# DM1090FFC_Power_Supply.net
KiCad netlist of a schematic drawn in Altium Designer
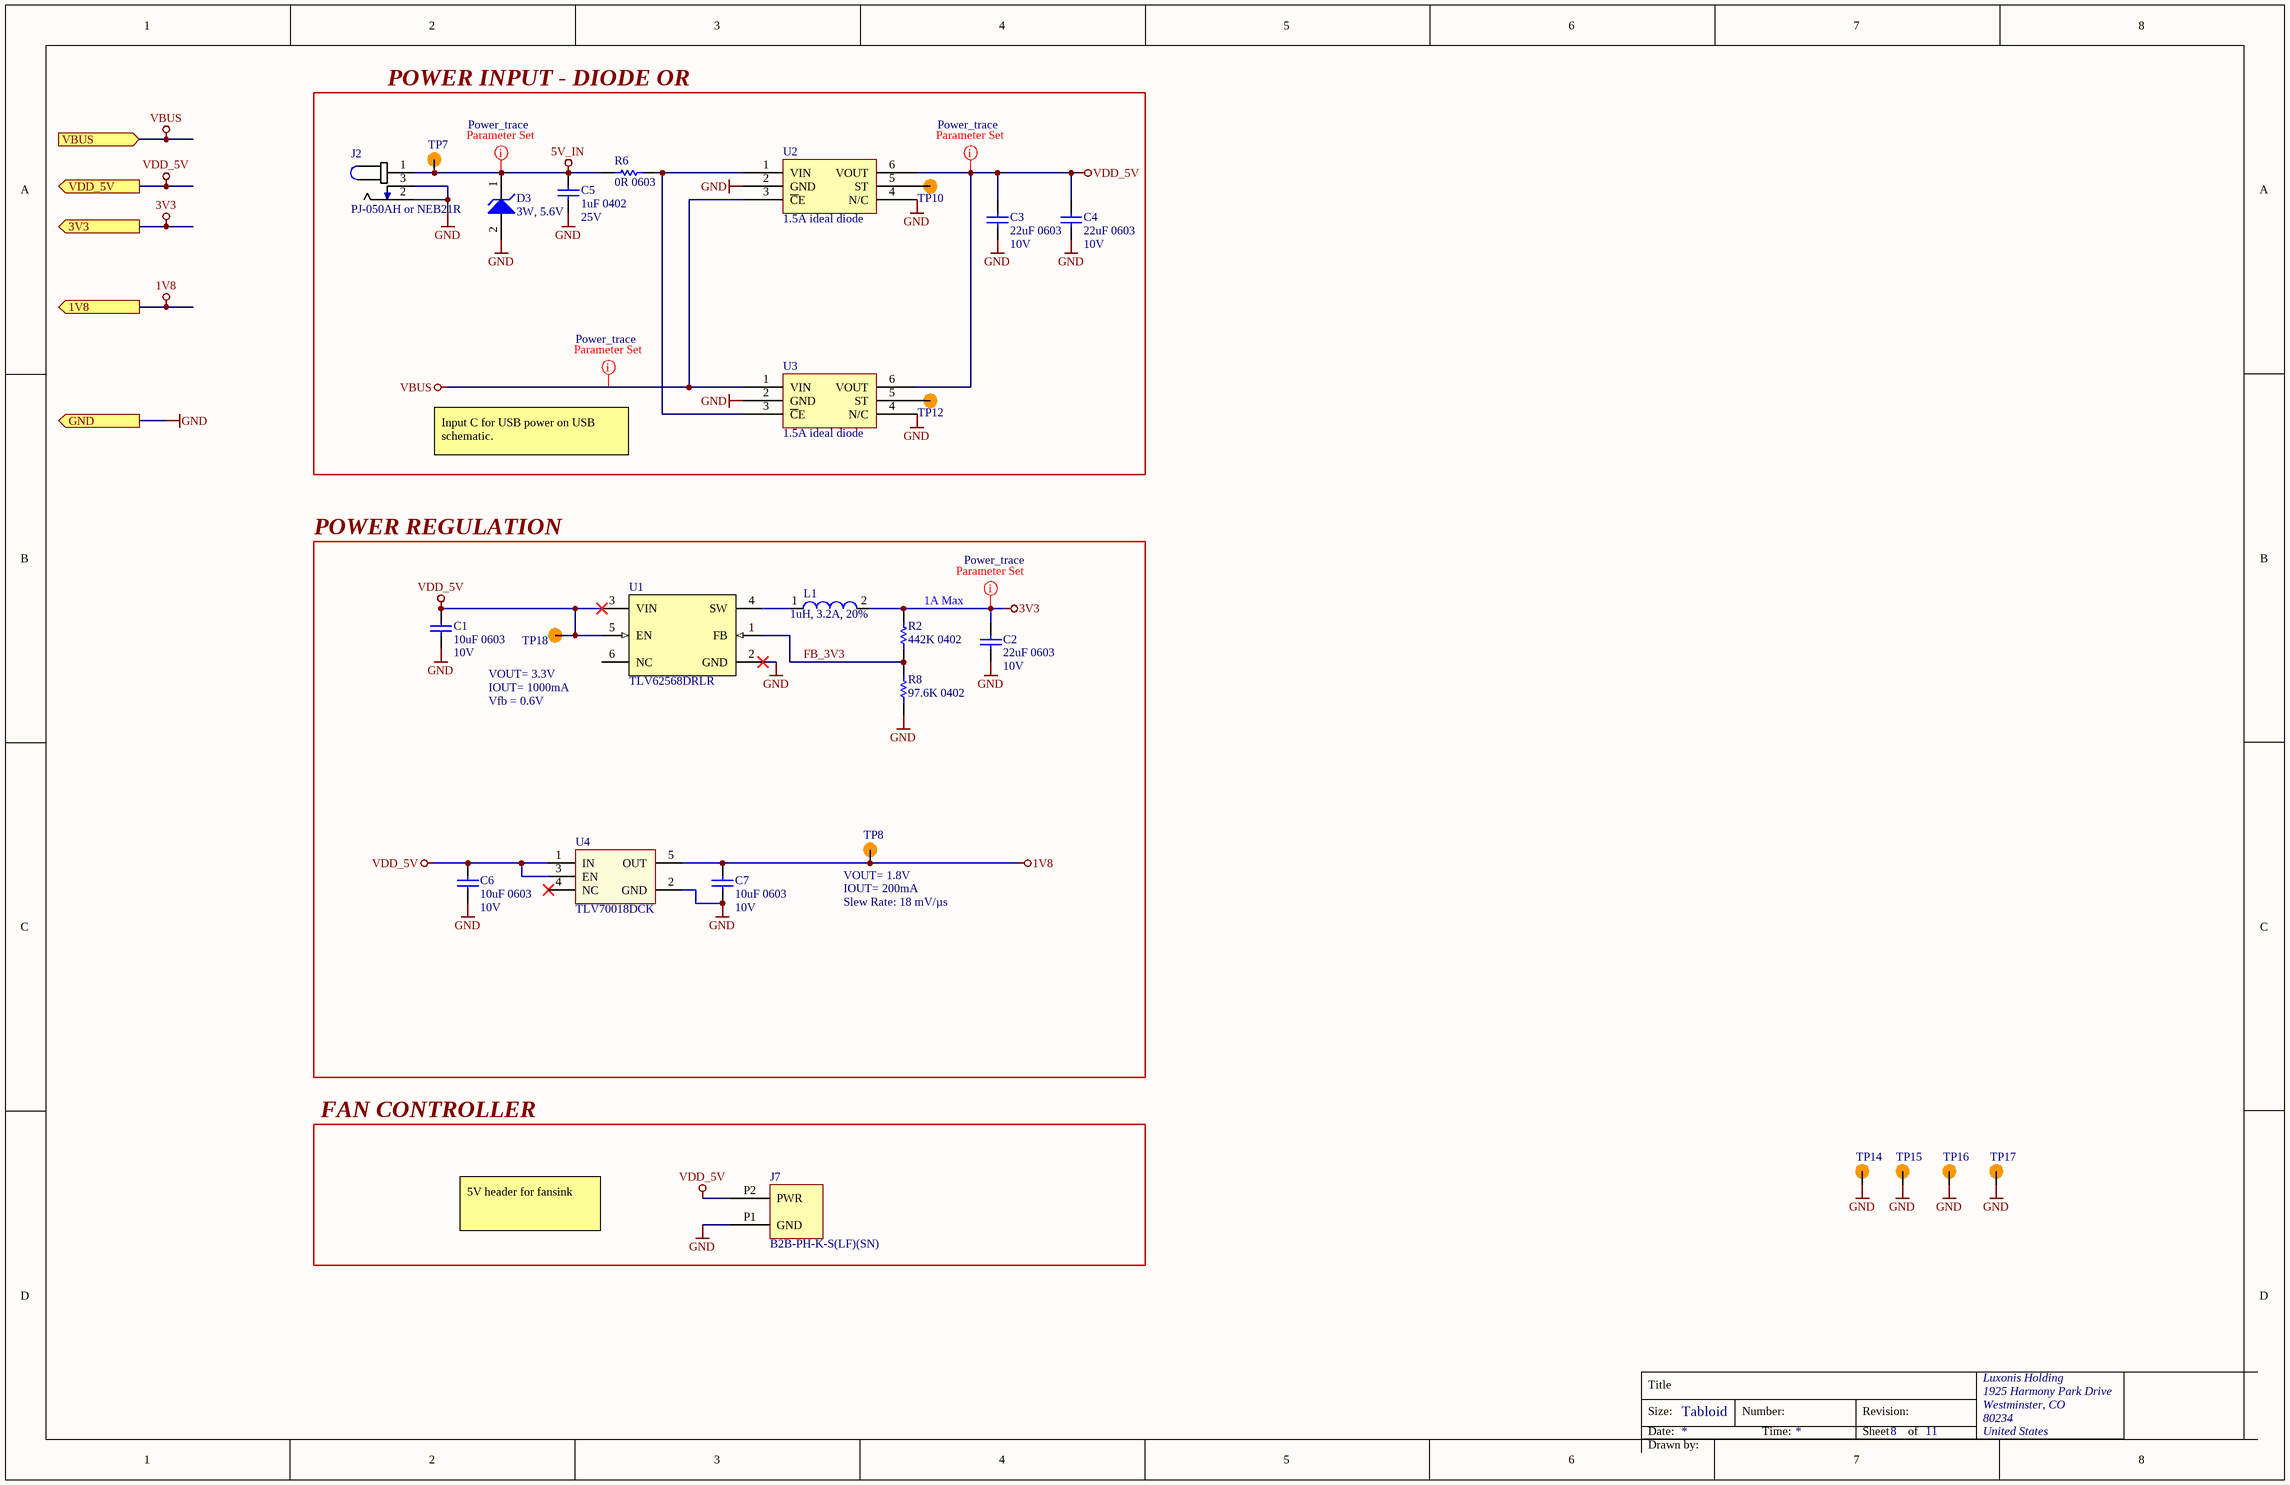
[diagram p0: DM1090FFC_Power_Supply.SchDoc]

(export (version "E")
  (design (tool "Eeschema 10.0.6"))
  (components
    (comp (ref "C1")
      (value "10uF 0603")
      (footprint "CAP_Altium_Vault_Generic:CAPC0603(1608)100_L")
      (description "CAP CER 10UF 10V X5R 0603 20%")
      (fields (field (name "TOLERANCE") "20%") (field (name "VOLTAGE RATING") "10V"))
      (libsource (lib "LuxonisMaster") (part "GRM188R61A106ME69D"))
    )
    (comp (ref "C2")
      (value "22uF 0603")
      (footprint "CAP_Altium_Vault_Generic:CAPC0603(1608)100_N")
      (description "CAP CER 22UF 10V X5R 0603 20%")
      (fields (field (name "TOLERANCE") "20%") (field (name "VOLTAGE RATING") "10V"))
      (libsource (lib "LuxonisMaster") (part "GRM188R61A226ME15D"))
    )
    (comp (ref "C3")
      (value "22uF 0603")
      (footprint "CAP_Altium_Vault_Generic:CAPC0603(1608)100_N")
      (description "CAP CER 22UF 10V X5R 0603 20%")
      (fields (field (name "TOLERANCE") "20%") (field (name "VOLTAGE RATING") "10V"))
      (libsource (lib "LuxonisMaster") (part "GRM188R61A226ME15D"))
    )
    (comp (ref "C4")
      (value "22uF 0603")
      (footprint "CAP_Altium_Vault_Generic:CAPC0603(1608)100_N")
      (description "CAP CER 22UF 10V X5R 0603 20%")
      (fields (field (name "TOLERANCE") "20%") (field (name "VOLTAGE RATING") "10V"))
      (libsource (lib "LuxonisMaster") (part "GRM188R61A226ME15D"))
    )
    (comp (ref "C5")
      (value "1uF 0402")
      (footprint "CAP_Altium_Vault_Generic:CAPC0402(1005)70_N")
      (description "CAP CER 1UF 25V X5R 0402 10%")
      (fields
        (field (name "TOLERANCE") "10%")
        (field (name "VOLTAGE") "25V")
        (field (name "VOLTAGE RATING") "25V")
      )
      (libsource (lib "LuxonisMaster") (part "GRM155R61E105KA12D"))
    )
    (comp (ref "C6")
      (value "10uF 0603")
      (footprint "CAP_Altium_Vault_Generic:CAPC0603(1608)100_L")
      (description "CAP CER 10UF 10V X5R 0603 20%")
      (fields (field (name "TOLERANCE") "20%") (field (name "VOLTAGE RATING") "10V"))
      (libsource (lib "LuxonisMaster") (part "GRM188R61A106ME69D"))
    )
    (comp (ref "C7")
      (value "10uF 0603")
      (footprint "CAP_Altium_Vault_Generic:CAPC0603(1608)100_L")
      (description "CAP CER 10UF 10V X5R 0603 20%")
      (fields (field (name "TOLERANCE") "20%") (field (name "VOLTAGE RATING") "10V"))
      (libsource (lib "LuxonisMaster") (part "GRM188R61A106ME69D"))
    )
    (comp (ref "D3")
      (value "3W, 5.6V")
      (footprint "DM1092_R0M0E0:1SMB5919BT3G")
      (description "DIODE ZENER 5.6V 3W SMB")
      (fields (field (name "TOLERANCE") "5%"))
      (libsource (lib "DM1092_R0M0E0") (part "1SMB5919BT3G"))
    )
    (comp (ref "J2")
      (value "PJ-050AH or NEB21R")
      (footprint "LuxonisMaster:PJ-050AH/NEB21R_COMBO")
      (description "CONN POWER PIN 2 POS RA PTH Barrel jack 2.1mm x 5.5mm combo footprint")
      (libsource (lib "LuxonisMaster") (part "PJ-050AH/NEB21R_COMBO"))
    )
    (comp (ref "J7")
      (value "B2B-PH-K-S(LF)(SN)")
      (footprint "LuxonisMaster:B2B-PH-K-S(LF)(SN)")
      (description "CONN HEADER VERT 2POS 2MM")
      (libsource (lib "LuxonisMaster") (part "B2B-PH-K-S(LF)(SN)"))
    )
    (comp (ref "L1")
      (value "1uH, 3.2A, 20%")
      (footprint "LuxonisMaster:DFE252012P-1R0M=P2")
      (description "FIXED IND 1UH 3.2A 42 MOHM SMD")
      (fields
        (field (name "MANUFACTURER") "Murata")
        (field (name "MANUFACTURER PART NUMBER") "DFE252012P-1R0M=P2")
      )
      (libsource (lib "LuxonisMaster") (part "DFE252012P-1R0M=P2"))
    )
    (comp (ref "R2")
      (value "442K 0402")
      (footprint "RES_Altium_Vault_Generic:RESC0402(1005)_N")
      (description "RES SMD 442K OHM 1% 1/16W 0402")
      (fields (field (name "TOLERANCE") "1%"))
      (libsource (lib "BW1092_R0M0E0") (part "CRCW0402442KFKED"))
    )
    (comp (ref "R6")
      (value "0R 0603")
      (footprint "RES_Altium_Vault_Generic:RESC0603(1608)_N")
      (fields (field (name "TOLERANCE") "5%"))
      (libsource (lib "LuxonisMaster") (part "CRCW06030000Z0EA"))
    )
    (comp (ref "R8")
      (value "97.6K 0402")
      (footprint "RES_Altium_Vault_Generic:RESC0402(1005)_N")
      (description "RES SMD 97.6K OHM 1% 1/16W 0402")
      (fields (field (name "TOLERANCE") "1%"))
      (libsource (lib "BW1092_R0M0E0") (part "CRCW040297K6FKED"))
    )
    (comp (ref "TP7")
      (value "TP100_200_NS")
      (footprint "LuxonisMaster:TP100_200_NS")
      (libsource (lib "LuxonisMaster") (part "TEST_POINT"))
    )
    (comp (ref "TP8")
      (value "TP100_200_NS")
      (footprint "LuxonisMaster:TP100_200_NS")
      (libsource (lib "LuxonisMaster") (part "TEST_POINT"))
    )
    (comp (ref "TP10")
      (value "TP100_200_NS")
      (footprint "LuxonisMaster:TP100_200_NS")
      (libsource (lib "LuxonisMaster") (part "TEST_POINT"))
    )
    (comp (ref "TP12")
      (value "TP100_200_NS")
      (footprint "LuxonisMaster:TP100_200_NS")
      (libsource (lib "LuxonisMaster") (part "TEST_POINT"))
    )
    (comp (ref "TP14")
      (value "TP100_200_NS")
      (footprint "LuxonisMaster:TP100_200_NS")
      (libsource (lib "LuxonisMaster") (part "TEST_POINT"))
    )
    (comp (ref "TP15")
      (value "TP100_200_NS")
      (footprint "LuxonisMaster:TP100_200_NS")
      (libsource (lib "LuxonisMaster") (part "TEST_POINT"))
    )
    (comp (ref "TP16")
      (value "TP100_200_NS")
      (footprint "LuxonisMaster:TP100_200_NS")
      (libsource (lib "LuxonisMaster") (part "TEST_POINT"))
    )
    (comp (ref "TP17")
      (value "TP100_200_NS")
      (footprint "LuxonisMaster:TP100_200_NS")
      (libsource (lib "LuxonisMaster") (part "TEST_POINT"))
    )
    (comp (ref "TP18")
      (value "TP100_200_NS")
      (footprint "LuxonisMaster:TP100_200_NS")
      (libsource (lib "LuxonisMaster") (part "TEST_POINT"))
    )
    (comp (ref "U1")
      (value "TLV62568DRLR")
      (footprint "DM1092_R0M0E0:TLV62568DRLR")
      (description "IC REG BUCK ADJ 1A SOT563-6")
      (libsource (lib "BW1092_R0M0E0") (part "TLV62568DRLR"))
    )
    (comp (ref "U2")
      (value "1.5A ideal diode")
      (footprint "LuxonisMaster:LM66100DCKR")
      (description "IC OR CTRLR IDEAL DIODE SC70-6")
      (libsource (lib "LuxonisMaster") (part "LM66100DCKR"))
    )
    (comp (ref "U3")
      (value "1.5A ideal diode")
      (footprint "LuxonisMaster:LM66100DCKR")
      (description "IC OR CTRLR IDEAL DIODE SC70-6")
      (libsource (lib "LuxonisMaster") (part "LM66100DCKR"))
    )
    (comp (ref "U4")
      (value "TLV70018DCK")
      (footprint "LuxonisMaster:TLV70018DCK")
      (description "IC REG LINEAR 1.8V 200MA SC70-5 Linear Voltage Regulator IC  1 Output  200mA SC-70-5")
      (libsource (lib "LuxonisMaster") (part "TLV70018DCK"))
    )
  )
  (nets
    (net (code "1") (name "/FB_3V3") (class "Default")
      (node (ref "R2") (pin "1") (pinfunction "1_1") (pintype "passive"))
      (node (ref "R8") (pin "2") (pinfunction "2_2") (pintype "passive"))
      (node (ref "U1") (pin "1") (pinfunction "FB_1") (pintype "input"))
    )
    (net (code "2") (name "1V8") (class "Default")
      (node (ref "C7") (pin "2") (pinfunction "2_2") (pintype "passive"))
      (node (ref "TP8") (pin "1") (pintype "passive"))
      (node (ref "U4") (pin "5") (pinfunction "OUT_5") (pintype "passive"))
    )
    (net (code "3") (name "3V3") (class "Default")
      (node (ref "C2") (pin "1") (pinfunction "1_1") (pintype "passive"))
      (node (ref "L1") (pin "2") (pinfunction "2_2") (pintype "passive"))
      (node (ref "R2") (pin "2") (pinfunction "2_2") (pintype "passive"))
    )
    (net (code "4") (name "5V_IN") (class "Default")
      (node (ref "C5") (pin "2") (pinfunction "2_2") (pintype "passive"))
      (node (ref "D3") (pin "1") (pinfunction "K_1") (pintype "passive"))
      (node (ref "J2") (pin "1") (pinfunction "1_1") (pintype "passive"))
      (node (ref "R6") (pin "1") (pinfunction "1_1") (pintype "passive"))
      (node (ref "TP7") (pin "1") (pintype "passive"))
    )
    (net (code "5") (name "GND") (class "Default")
      (node (ref "C1") (pin "1") (pinfunction "1_1") (pintype "passive"))
      (node (ref "C2") (pin "2") (pinfunction "2_2") (pintype "passive"))
      (node (ref "C3") (pin "1") (pinfunction "1_1") (pintype "passive"))
      (node (ref "C4") (pin "1") (pinfunction "1_1") (pintype "passive"))
      (node (ref "C5") (pin "1") (pinfunction "1_1") (pintype "passive"))
      (node (ref "C6") (pin "1") (pinfunction "1_1") (pintype "passive"))
      (node (ref "C7") (pin "1") (pinfunction "1_1") (pintype "passive"))
      (node (ref "D3") (pin "2") (pinfunction "A_2") (pintype "passive"))
      (node (ref "J2") (pin "2") (pinfunction "2_2") (pintype "passive"))
      (node (ref "J2") (pin "3") (pinfunction "3_3") (pintype "passive"))
      (node (ref "J7") (pin "P1") (pinfunction "GND_P1") (pintype "passive"))
      (node (ref "R8") (pin "1") (pinfunction "1_1") (pintype "passive"))
      (node (ref "TP14") (pin "1") (pintype "passive"))
      (node (ref "TP15") (pin "1") (pintype "passive"))
      (node (ref "TP16") (pin "1") (pintype "passive"))
      (node (ref "TP17") (pin "1") (pintype "passive"))
      (node (ref "U1") (pin "2") (pinfunction "GND_2") (pintype "power_in"))
      (node (ref "U2") (pin "2") (pinfunction "GND_2") (pintype "passive"))
      (node (ref "U2") (pin "4") (pinfunction "N/C_4") (pintype "passive"))
      (node (ref "U3") (pin "2") (pinfunction "GND_2") (pintype "passive"))
      (node (ref "U3") (pin "4") (pinfunction "N/C_4") (pintype "passive"))
      (node (ref "U4") (pin "2") (pinfunction "GND_2") (pintype "passive"))
    )
    (net (code "6") (name "Net-(U1-SW)") (class "Default")
      (node (ref "L1") (pin "1") (pinfunction "1_1") (pintype "passive"))
      (node (ref "U1") (pin "4") (pinfunction "SW_4") (pintype "power_in"))
    )
    (net (code "7") (name "Net-(U2-ST)") (class "Default")
      (node (ref "TP10") (pin "1") (pintype "passive"))
      (node (ref "U2") (pin "5") (pinfunction "ST_5") (pintype "passive"))
    )
    (net (code "8") (name "Net-(U2-VIN)") (class "Default")
      (node (ref "R6") (pin "2") (pinfunction "2_2") (pintype "passive"))
      (node (ref "U2") (pin "1") (pinfunction "VIN_1") (pintype "passive"))
      (node (ref "U3") (pin "3") (pinfunction "~{C}E_3") (pintype "passive"))
    )
    (net (code "9") (name "Net-(U3-ST)") (class "Default")
      (node (ref "TP12") (pin "1") (pintype "passive"))
      (node (ref "U3") (pin "5") (pinfunction "ST_5") (pintype "passive"))
    )
    (net (code "10") (name "VBUS") (class "Default")
      (node (ref "U2") (pin "3") (pinfunction "~{C}E_3") (pintype "passive"))
      (node (ref "U3") (pin "1") (pinfunction "VIN_1") (pintype "passive"))
    )
    (net (code "11") (name "VDD_5V") (class "Default")
      (node (ref "C1") (pin "2") (pinfunction "2_2") (pintype "passive"))
      (node (ref "C3") (pin "2") (pinfunction "2_2") (pintype "passive"))
      (node (ref "C4") (pin "2") (pinfunction "2_2") (pintype "passive"))
      (node (ref "C6") (pin "2") (pinfunction "2_2") (pintype "passive"))
      (node (ref "J7") (pin "P2") (pinfunction "PWR_P2") (pintype "passive"))
      (node (ref "TP18") (pin "1") (pintype "passive"))
      (node (ref "U1") (pin "3") (pinfunction "VIN_3") (pintype "power_in"))
      (node (ref "U1") (pin "5") (pinfunction "EN_5") (pintype "input"))
      (node (ref "U2") (pin "6") (pinfunction "VOUT_6") (pintype "passive"))
      (node (ref "U3") (pin "6") (pinfunction "VOUT_6") (pintype "passive"))
      (node (ref "U4") (pin "1") (pinfunction "IN_1") (pintype "passive"))
      (node (ref "U4") (pin "3") (pinfunction "EN_3") (pintype "passive"))
    )
    (net (code "12") (name "unconnected-(U1-NC-Pad6)") (class "Default")
      (node (ref "U1") (pin "6") (pinfunction "NC_6") (pintype "passive"))
    )
    (net (code "13") (name "unconnected-(U4-NC-Pad4)") (class "Default")
      (node (ref "U4") (pin "4") (pinfunction "NC_4") (pintype "passive+no_connect"))
    )
  )
)
